# Sheet1.net
KiCad netlist of a schematic drawn in Altium Designer
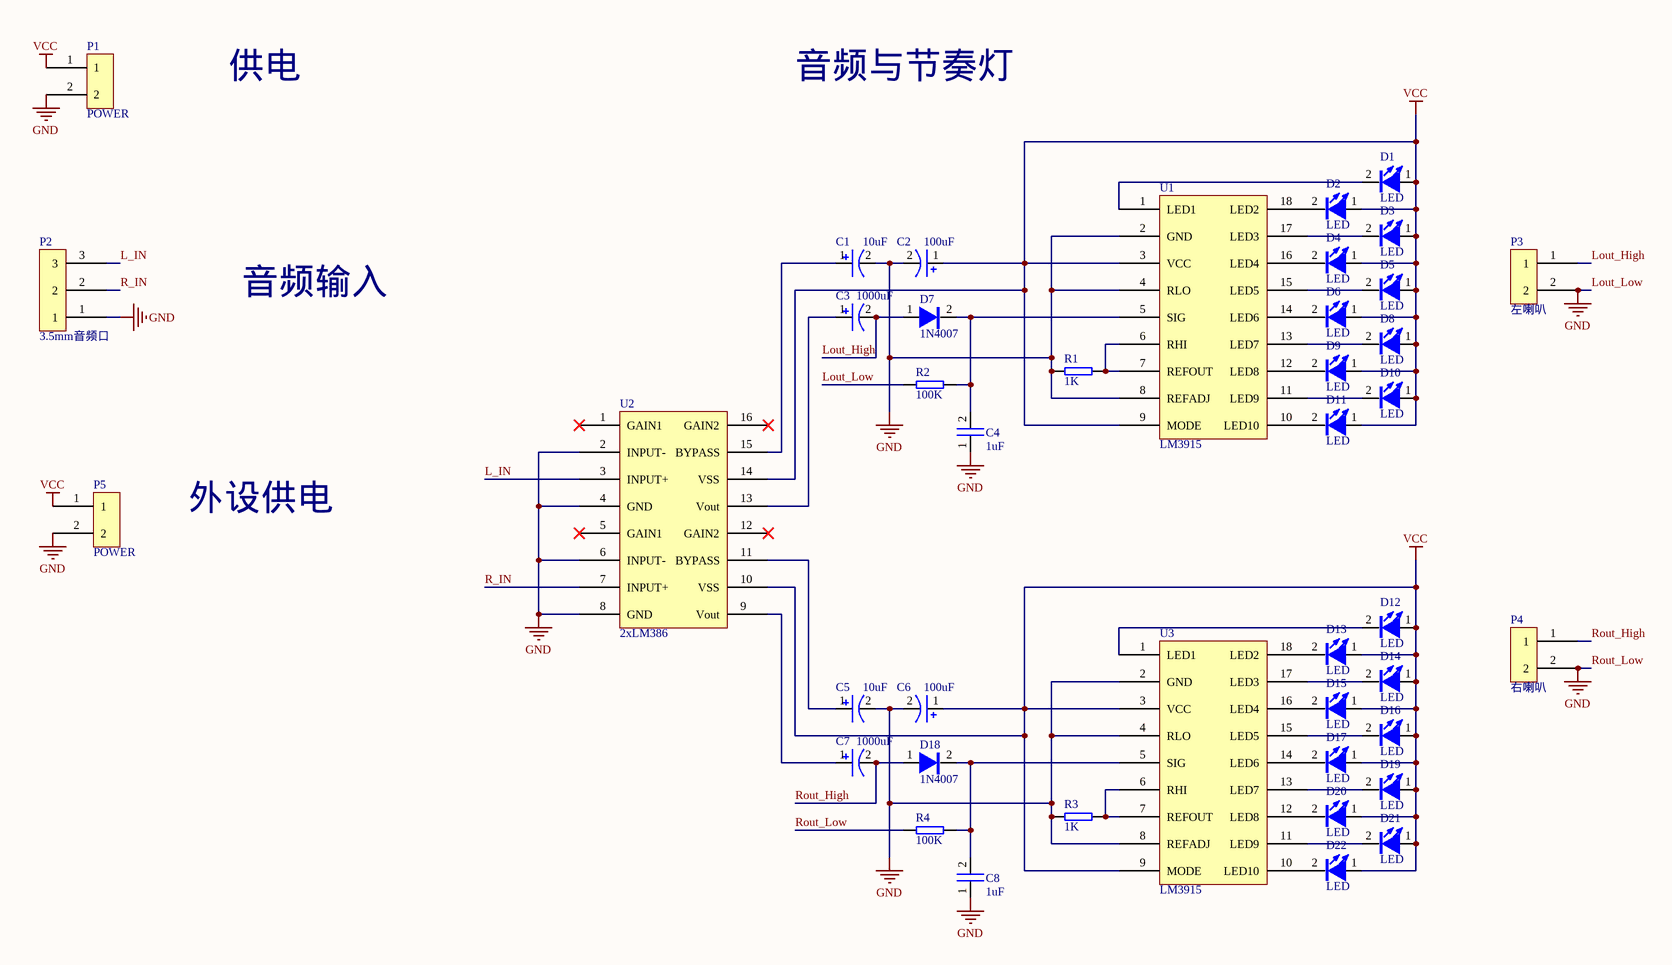
[diagram p0: Sheet1.SchDoc]

(export (version "E")
  (design (tool "Eeschema 10.0.6"))
  (components
    (comp (ref "C1")
      (value "10uF")
      (footprint "极性电容_2.54mm直插 - duplicate")
      (description "电容_极性")
      (libsource (lib "Schlib1") (part "ECAP"))
    )
    (comp (ref "C2")
      (value "100uF")
      (footprint "极性电容_2.54mm直插 - duplicate")
      (description "电容_极性")
      (libsource (lib "Schlib1") (part "ECAP"))
    )
    (comp (ref "C3")
      (value "1000uF")
      (footprint "极性电容_2.54mm直插 - duplicate")
      (description "电容_极性")
      (libsource (lib "Schlib1") (part "ECAP"))
    )
    (comp (ref "C4")
      (value "1uF")
      (footprint "电容104")
      (description "电容_普通")
      (libsource (lib "Schlib1") (part "CAP"))
    )
    (comp (ref "C5")
      (value "10uF")
      (footprint "极性电容_2.54mm直插 - duplicate")
      (description "电容_极性")
      (libsource (lib "Schlib1") (part "ECAP"))
    )
    (comp (ref "C6")
      (value "100uF")
      (footprint "极性电容_2.54mm直插 - duplicate")
      (description "电容_极性")
      (libsource (lib "Schlib1") (part "ECAP"))
    )
    (comp (ref "C7")
      (value "1000uF")
      (footprint "极性电容_2.54mm直插 - duplicate")
      (description "电容_极性")
      (libsource (lib "Schlib1") (part "ECAP"))
    )
    (comp (ref "C8")
      (value "1uF")
      (footprint "电容104")
      (description "电容_普通")
      (libsource (lib "Schlib1") (part "CAP"))
    )
    (comp (ref "D1")
      (value "LED")
      (footprint "LED")
      (description "二极管_发光")
      (libsource (lib "Schlib1") (part "LED"))
    )
    (comp (ref "D2")
      (value "LED")
      (footprint "LED")
      (description "二极管_发光")
      (libsource (lib "Schlib1") (part "LED"))
    )
    (comp (ref "D3")
      (value "LED")
      (footprint "LED")
      (description "二极管_发光")
      (libsource (lib "Schlib1") (part "LED"))
    )
    (comp (ref "D4")
      (value "LED")
      (footprint "LED")
      (description "二极管_发光")
      (libsource (lib "Schlib1") (part "LED"))
    )
    (comp (ref "D5")
      (value "LED")
      (footprint "LED")
      (description "二极管_发光")
      (libsource (lib "Schlib1") (part "LED"))
    )
    (comp (ref "D6")
      (value "LED")
      (footprint "LED")
      (description "二极管_发光")
      (libsource (lib "Schlib1") (part "LED"))
    )
    (comp (ref "D7")
      (value "1N4007")
      (footprint "二极管1N4007")
      (description "二极管_普通")
      (libsource (lib "Schlib1") (part "DIO"))
    )
    (comp (ref "D8")
      (value "LED")
      (footprint "led")
      (description "二极管_发光")
      (libsource (lib "Schlib1") (part "LED"))
    )
    (comp (ref "D9")
      (value "LED")
      (footprint "led")
      (description "二极管_发光")
      (libsource (lib "Schlib1") (part "LED"))
    )
    (comp (ref "D10")
      (value "LED")
      (footprint "led")
      (description "二极管_发光")
      (libsource (lib "Schlib1") (part "LED"))
    )
    (comp (ref "D11")
      (value "LED")
      (footprint "led")
      (description "二极管_发光")
      (libsource (lib "Schlib1") (part "LED"))
    )
    (comp (ref "D12")
      (value "LED")
      (footprint "LED")
      (description "二极管_发光")
      (libsource (lib "Schlib1") (part "LED"))
    )
    (comp (ref "D13")
      (value "LED")
      (footprint "LED")
      (description "二极管_发光")
      (libsource (lib "Schlib1") (part "LED"))
    )
    (comp (ref "D14")
      (value "LED")
      (footprint "LED")
      (description "二极管_发光")
      (libsource (lib "Schlib1") (part "LED"))
    )
    (comp (ref "D15")
      (value "LED")
      (footprint "LED")
      (description "二极管_发光")
      (libsource (lib "Schlib1") (part "LED"))
    )
    (comp (ref "D16")
      (value "LED")
      (footprint "LED")
      (description "二极管_发光")
      (libsource (lib "Schlib1") (part "LED"))
    )
    (comp (ref "D17")
      (value "LED")
      (footprint "LED")
      (description "二极管_发光")
      (libsource (lib "Schlib1") (part "LED"))
    )
    (comp (ref "D18")
      (value "1N4007")
      (footprint "二极管1N4007")
      (description "二极管_普通")
      (libsource (lib "Schlib1") (part "DIO"))
    )
    (comp (ref "D19")
      (value "LED")
      (footprint "led")
      (description "二极管_发光")
      (libsource (lib "Schlib1") (part "LED"))
    )
    (comp (ref "D20")
      (value "LED")
      (footprint "led")
      (description "二极管_发光")
      (libsource (lib "Schlib1") (part "LED"))
    )
    (comp (ref "D21")
      (value "LED")
      (footprint "led")
      (description "二极管_发光")
      (libsource (lib "Schlib1") (part "LED"))
    )
    (comp (ref "D22")
      (value "LED")
      (footprint "led")
      (description "二极管_发光")
      (libsource (lib "Schlib1") (part "LED"))
    )
    (comp (ref "P1")
      (value "POWER")
      (footprint "2Pin_Type-C正")
      (description "2Pin插针")
      (libsource (lib "") (part "PIN2_1"))
    )
    (comp (ref "P2")
      (value "3.5mm音频口")
      (footprint "3.5耳机孔_小")
      (description "3Pin插针")
      (libsource (lib "Schlib1") (part "PIN3"))
    )
    (comp (ref "P3")
      (value "左喇叭")
      (footprint "2pin插针")
      (description "2Pin插针")
      (libsource (lib "Schlib1") (part "PIN2"))
    )
    (comp (ref "P4")
      (value "右喇叭")
      (footprint "2pin插针")
      (description "2Pin插针")
      (libsource (lib "Schlib1") (part "PIN2"))
    )
    (comp (ref "P5")
      (value "POWER")
      (footprint "2pin插针")
      (description "2Pin插针")
      (libsource (lib "") (part "PIN2_1"))
    )
    (comp (ref "R1")
      (value "1K")
      (footprint "7.62mm直插")
      (description "电阻")
      (libsource (lib "Schlib1") (part "RES"))
    )
    (comp (ref "R2")
      (value "100K")
      (footprint "7.62mm直插")
      (description "电阻")
      (libsource (lib "Schlib1") (part "RES"))
    )
    (comp (ref "R3")
      (value "1K")
      (footprint "7.62mm直插")
      (description "电阻")
      (libsource (lib "Schlib1") (part "RES"))
    )
    (comp (ref "R4")
      (value "100K")
      (footprint "7.62mm直插")
      (description "电阻")
      (libsource (lib "Schlib1") (part "RES"))
    )
    (comp (ref "U1")
      (value "LM3915")
      (footprint "9Pin插座_18")
      (description "LED驱动IC")
      (libsource (lib "Schlib1") (part "LM3915"))
    )
    (comp (ref "U2")
      (value "2xLM386")
      (footprint "2xLM386")
      (description "两个LM386")
      (libsource (lib "Schlib1") (part "2xLM386"))
    )
    (comp (ref "U3")
      (value "LM3915")
      (footprint "9Pin插座_18")
      (description "LED驱动IC")
      (libsource (lib "Schlib1") (part "LM3915"))
    )
  )
  (nets
    (net (code "1") (name "/L_IN") (class "Default")
      (node (ref "P2") (pin "3") (pinfunction "3_3") (pintype "passive"))
      (node (ref "U2") (pin "3") (pinfunction "INPUT+_3") (pintype "passive"))
    )
    (net (code "2") (name "/Lout_High") (class "Default")
      (node (ref "C3") (pin "2") (pinfunction "-_2") (pintype "passive"))
      (node (ref "D7") (pin "1") (pinfunction "1_1") (pintype "passive"))
      (node (ref "P3") (pin "1") (pinfunction "1_1") (pintype "passive"))
    )
    (net (code "3") (name "/R_IN") (class "Default")
      (node (ref "P2") (pin "2") (pinfunction "2_2") (pintype "passive"))
      (node (ref "U2") (pin "7") (pinfunction "INPUT+_7") (pintype "passive"))
    )
    (net (code "4") (name "/Rout_High") (class "Default")
      (node (ref "C7") (pin "2") (pinfunction "-_2") (pintype "passive"))
      (node (ref "D18") (pin "1") (pinfunction "1_1") (pintype "passive"))
      (node (ref "P4") (pin "1") (pinfunction "1_1") (pintype "passive"))
    )
    (net (code "5") (name "GND") (class "Default")
      (node (ref "C1") (pin "2") (pinfunction "-_2") (pintype "passive"))
      (node (ref "C2") (pin "2") (pinfunction "-_2") (pintype "passive"))
      (node (ref "C4") (pin "1") (pinfunction "1_1") (pintype "passive"))
      (node (ref "C5") (pin "2") (pinfunction "-_2") (pintype "passive"))
      (node (ref "C6") (pin "2") (pinfunction "-_2") (pintype "passive"))
      (node (ref "C8") (pin "1") (pinfunction "1_1") (pintype "passive"))
      (node (ref "P1") (pin "2") (pinfunction "2_2") (pintype "passive"))
      (node (ref "P2") (pin "1") (pinfunction "1_1") (pintype "passive"))
      (node (ref "P3") (pin "2") (pinfunction "2_2") (pintype "passive"))
      (node (ref "P4") (pin "2") (pinfunction "2_2") (pintype "passive"))
      (node (ref "P5") (pin "2") (pinfunction "2_2") (pintype "passive"))
      (node (ref "R1") (pin "1") (pinfunction "1_1") (pintype "passive"))
      (node (ref "R2") (pin "1") (pinfunction "1_1") (pintype "passive"))
      (node (ref "R3") (pin "1") (pinfunction "1_1") (pintype "passive"))
      (node (ref "R4") (pin "1") (pinfunction "1_1") (pintype "passive"))
      (node (ref "U1") (pin "2") (pinfunction "GND_2") (pintype "passive"))
      (node (ref "U1") (pin "4") (pinfunction "RLO_4") (pintype "passive"))
      (node (ref "U1") (pin "8") (pinfunction "REFADJ_8") (pintype "passive"))
      (node (ref "U2") (pin "2") (pinfunction "INPUT-_2") (pintype "passive"))
      (node (ref "U2") (pin "4") (pinfunction "GND_4") (pintype "passive"))
      (node (ref "U2") (pin "6") (pinfunction "INPUT-_6") (pintype "passive"))
      (node (ref "U2") (pin "8") (pinfunction "GND_8") (pintype "passive"))
      (node (ref "U3") (pin "2") (pinfunction "GND_2") (pintype "passive"))
      (node (ref "U3") (pin "4") (pinfunction "RLO_4") (pintype "passive"))
      (node (ref "U3") (pin "8") (pinfunction "REFADJ_8") (pintype "passive"))
    )
    (net (code "6") (name "Net-(C1-+)") (class "Default")
      (node (ref "C1") (pin "1") (pinfunction "+_1") (pintype "passive"))
      (node (ref "U2") (pin "15") (pinfunction "BYPASS_15") (pintype "passive"))
    )
    (net (code "7") (name "Net-(C3-+)") (class "Default")
      (node (ref "C3") (pin "1") (pinfunction "+_1") (pintype "passive"))
      (node (ref "U2") (pin "13") (pinfunction "Vout_13") (pintype "passive"))
    )
    (net (code "8") (name "Net-(C5-+)") (class "Default")
      (node (ref "C5") (pin "1") (pinfunction "+_1") (pintype "passive"))
      (node (ref "U2") (pin "11") (pinfunction "BYPASS_11") (pintype "passive"))
    )
    (net (code "9") (name "Net-(C7-+)") (class "Default")
      (node (ref "C7") (pin "1") (pinfunction "+_1") (pintype "passive"))
      (node (ref "U2") (pin "9") (pinfunction "Vout_9") (pintype "passive"))
    )
    (net (code "10") (name "Net-(U1-LED1)") (class "Default")
      (node (ref "D1") (pin "2") (pinfunction "2_2") (pintype "passive"))
      (node (ref "U1") (pin "1") (pinfunction "LED1_1") (pintype "passive"))
    )
    (net (code "11") (name "Net-(U1-LED2)") (class "Default")
      (node (ref "D2") (pin "2") (pinfunction "2_2") (pintype "passive"))
      (node (ref "U1") (pin "18") (pinfunction "LED2_18") (pintype "passive"))
    )
    (net (code "12") (name "Net-(U1-LED3)") (class "Default")
      (node (ref "D3") (pin "2") (pinfunction "2_2") (pintype "passive"))
      (node (ref "U1") (pin "17") (pinfunction "LED3_17") (pintype "passive"))
    )
    (net (code "13") (name "Net-(U1-LED4)") (class "Default")
      (node (ref "D4") (pin "2") (pinfunction "2_2") (pintype "passive"))
      (node (ref "U1") (pin "16") (pinfunction "LED4_16") (pintype "passive"))
    )
    (net (code "14") (name "Net-(U1-LED5)") (class "Default")
      (node (ref "D5") (pin "2") (pinfunction "2_2") (pintype "passive"))
      (node (ref "U1") (pin "15") (pinfunction "LED5_15") (pintype "passive"))
    )
    (net (code "15") (name "Net-(U1-LED6)") (class "Default")
      (node (ref "D6") (pin "2") (pinfunction "2_2") (pintype "passive"))
      (node (ref "U1") (pin "14") (pinfunction "LED6_14") (pintype "passive"))
    )
    (net (code "16") (name "Net-(U1-LED7)") (class "Default")
      (node (ref "D8") (pin "2") (pinfunction "2_2") (pintype "passive"))
      (node (ref "U1") (pin "13") (pinfunction "LED7_13") (pintype "passive"))
    )
    (net (code "17") (name "Net-(U1-LED8)") (class "Default")
      (node (ref "D9") (pin "2") (pinfunction "2_2") (pintype "passive"))
      (node (ref "U1") (pin "12") (pinfunction "LED8_12") (pintype "passive"))
    )
    (net (code "18") (name "Net-(U1-LED9)") (class "Default")
      (node (ref "D10") (pin "2") (pinfunction "2_2") (pintype "passive"))
      (node (ref "U1") (pin "11") (pinfunction "LED9_11") (pintype "passive"))
    )
    (net (code "19") (name "Net-(U1-LED10)") (class "Default")
      (node (ref "D11") (pin "2") (pinfunction "2_2") (pintype "passive"))
      (node (ref "U1") (pin "10") (pinfunction "LED10_10") (pintype "passive"))
    )
    (net (code "20") (name "Net-(U1-REFOUT)") (class "Default")
      (node (ref "R1") (pin "2") (pinfunction "2_2") (pintype "passive"))
      (node (ref "U1") (pin "6") (pinfunction "RHI_6") (pintype "passive"))
      (node (ref "U1") (pin "7") (pinfunction "REFOUT_7") (pintype "passive"))
    )
    (net (code "21") (name "Net-(U1-SIG)") (class "Default")
      (node (ref "C4") (pin "2") (pinfunction "2_2") (pintype "passive"))
      (node (ref "D7") (pin "2") (pinfunction "2_2") (pintype "passive"))
      (node (ref "R2") (pin "2") (pinfunction "2_2") (pintype "passive"))
      (node (ref "U1") (pin "5") (pinfunction "SIG_5") (pintype "passive"))
    )
    (net (code "22") (name "Net-(U3-LED1)") (class "Default")
      (node (ref "D12") (pin "2") (pinfunction "2_2") (pintype "passive"))
      (node (ref "U3") (pin "1") (pinfunction "LED1_1") (pintype "passive"))
    )
    (net (code "23") (name "Net-(U3-LED2)") (class "Default")
      (node (ref "D13") (pin "2") (pinfunction "2_2") (pintype "passive"))
      (node (ref "U3") (pin "18") (pinfunction "LED2_18") (pintype "passive"))
    )
    (net (code "24") (name "Net-(U3-LED3)") (class "Default")
      (node (ref "D14") (pin "2") (pinfunction "2_2") (pintype "passive"))
      (node (ref "U3") (pin "17") (pinfunction "LED3_17") (pintype "passive"))
    )
    (net (code "25") (name "Net-(U3-LED4)") (class "Default")
      (node (ref "D15") (pin "2") (pinfunction "2_2") (pintype "passive"))
      (node (ref "U3") (pin "16") (pinfunction "LED4_16") (pintype "passive"))
    )
    (net (code "26") (name "Net-(U3-LED5)") (class "Default")
      (node (ref "D16") (pin "2") (pinfunction "2_2") (pintype "passive"))
      (node (ref "U3") (pin "15") (pinfunction "LED5_15") (pintype "passive"))
    )
    (net (code "27") (name "Net-(U3-LED6)") (class "Default")
      (node (ref "D17") (pin "2") (pinfunction "2_2") (pintype "passive"))
      (node (ref "U3") (pin "14") (pinfunction "LED6_14") (pintype "passive"))
    )
    (net (code "28") (name "Net-(U3-LED7)") (class "Default")
      (node (ref "D19") (pin "2") (pinfunction "2_2") (pintype "passive"))
      (node (ref "U3") (pin "13") (pinfunction "LED7_13") (pintype "passive"))
    )
    (net (code "29") (name "Net-(U3-LED8)") (class "Default")
      (node (ref "D20") (pin "2") (pinfunction "2_2") (pintype "passive"))
      (node (ref "U3") (pin "12") (pinfunction "LED8_12") (pintype "passive"))
    )
    (net (code "30") (name "Net-(U3-LED9)") (class "Default")
      (node (ref "D21") (pin "2") (pinfunction "2_2") (pintype "passive"))
      (node (ref "U3") (pin "11") (pinfunction "LED9_11") (pintype "passive"))
    )
    (net (code "31") (name "Net-(U3-LED10)") (class "Default")
      (node (ref "D22") (pin "2") (pinfunction "2_2") (pintype "passive"))
      (node (ref "U3") (pin "10") (pinfunction "LED10_10") (pintype "passive"))
    )
    (net (code "32") (name "Net-(U3-REFOUT)") (class "Default")
      (node (ref "R3") (pin "2") (pinfunction "2_2") (pintype "passive"))
      (node (ref "U3") (pin "6") (pinfunction "RHI_6") (pintype "passive"))
      (node (ref "U3") (pin "7") (pinfunction "REFOUT_7") (pintype "passive"))
    )
    (net (code "33") (name "Net-(U3-SIG)") (class "Default")
      (node (ref "C8") (pin "2") (pinfunction "2_2") (pintype "passive"))
      (node (ref "D18") (pin "2") (pinfunction "2_2") (pintype "passive"))
      (node (ref "R4") (pin "2") (pinfunction "2_2") (pintype "passive"))
      (node (ref "U3") (pin "5") (pinfunction "SIG_5") (pintype "passive"))
    )
    (net (code "34") (name "VCC") (class "Default")
      (node (ref "C2") (pin "1") (pinfunction "+_1") (pintype "passive"))
      (node (ref "C6") (pin "1") (pinfunction "+_1") (pintype "passive"))
      (node (ref "D1") (pin "1") (pinfunction "1_1") (pintype "passive"))
      (node (ref "D10") (pin "1") (pinfunction "1_1") (pintype "passive"))
      (node (ref "D11") (pin "1") (pinfunction "1_1") (pintype "passive"))
      (node (ref "D12") (pin "1") (pinfunction "1_1") (pintype "passive"))
      (node (ref "D13") (pin "1") (pinfunction "1_1") (pintype "passive"))
      (node (ref "D14") (pin "1") (pinfunction "1_1") (pintype "passive"))
      (node (ref "D15") (pin "1") (pinfunction "1_1") (pintype "passive"))
      (node (ref "D16") (pin "1") (pinfunction "1_1") (pintype "passive"))
      (node (ref "D17") (pin "1") (pinfunction "1_1") (pintype "passive"))
      (node (ref "D19") (pin "1") (pinfunction "1_1") (pintype "passive"))
      (node (ref "D2") (pin "1") (pinfunction "1_1") (pintype "passive"))
      (node (ref "D20") (pin "1") (pinfunction "1_1") (pintype "passive"))
      (node (ref "D21") (pin "1") (pinfunction "1_1") (pintype "passive"))
      (node (ref "D22") (pin "1") (pinfunction "1_1") (pintype "passive"))
      (node (ref "D3") (pin "1") (pinfunction "1_1") (pintype "passive"))
      (node (ref "D4") (pin "1") (pinfunction "1_1") (pintype "passive"))
      (node (ref "D5") (pin "1") (pinfunction "1_1") (pintype "passive"))
      (node (ref "D6") (pin "1") (pinfunction "1_1") (pintype "passive"))
      (node (ref "D8") (pin "1") (pinfunction "1_1") (pintype "passive"))
      (node (ref "D9") (pin "1") (pinfunction "1_1") (pintype "passive"))
      (node (ref "P1") (pin "1") (pinfunction "1_1") (pintype "passive"))
      (node (ref "P5") (pin "1") (pinfunction "1_1") (pintype "passive"))
      (node (ref "U1") (pin "3") (pinfunction "VCC_3") (pintype "passive"))
      (node (ref "U1") (pin "9") (pinfunction "MODE_9") (pintype "passive"))
      (node (ref "U2") (pin "10") (pinfunction "VSS_10") (pintype "passive"))
      (node (ref "U2") (pin "14") (pinfunction "VSS_14") (pintype "passive"))
      (node (ref "U3") (pin "3") (pinfunction "VCC_3") (pintype "passive"))
      (node (ref "U3") (pin "9") (pinfunction "MODE_9") (pintype "passive"))
    )
    (net (code "35") (name "unconnected-(U2-GAIN1-Pad1)") (class "Default")
      (node (ref "U2") (pin "1") (pinfunction "GAIN1_1") (pintype "passive+no_connect"))
    )
    (net (code "36") (name "unconnected-(U2-GAIN1-Pad5)") (class "Default")
      (node (ref "U2") (pin "5") (pinfunction "GAIN1_5") (pintype "passive+no_connect"))
    )
    (net (code "37") (name "unconnected-(U2-GAIN2-Pad12)") (class "Default")
      (node (ref "U2") (pin "12") (pinfunction "GAIN2_12") (pintype "passive+no_connect"))
    )
    (net (code "38") (name "unconnected-(U2-GAIN2-Pad16)") (class "Default")
      (node (ref "U2") (pin "16") (pinfunction "GAIN2_16") (pintype "passive+no_connect"))
    )
  )
)
